# PDM.net
KiCad netlist of a schematic drawn in EAGLE
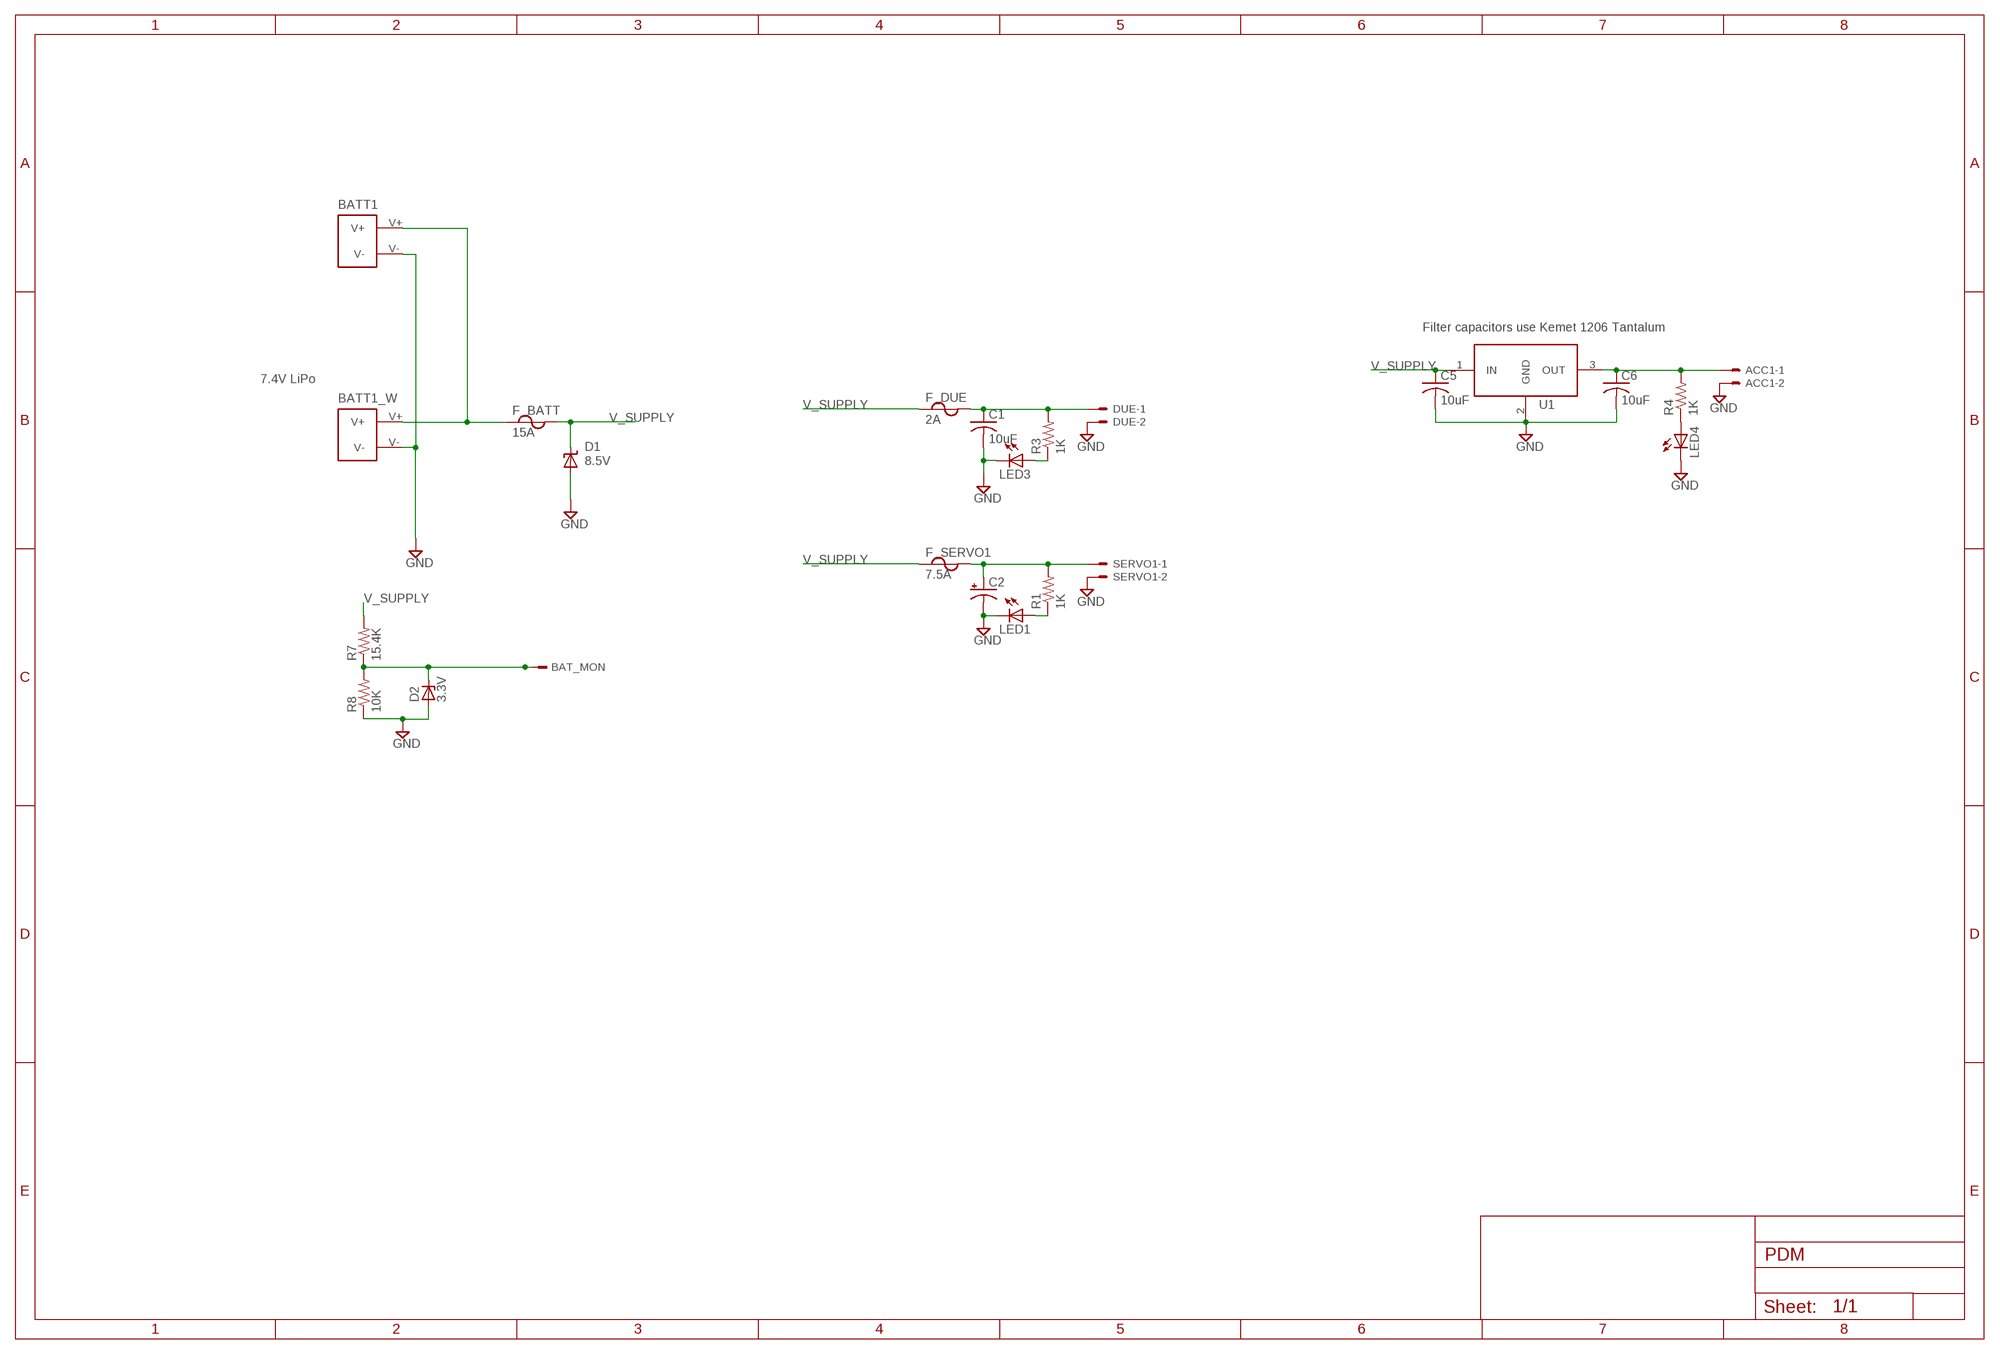
[diagram p0: schematic, sheet 1]

(export (version "E")
  (design (tool "Eeschema 10.0.6"))
  (components
    (comp (ref "ACC1")
      (value "5566-2")
      (footprint "eagle-import:5566-2")
      (libsource (lib "eagle-import") (part "5566-2"))
    )
    (comp (ref "BATT1")
      (value "CON_XT60-PCB_MOUNT")
      (footprint "eagle-import:CON_XT60_PCB_MOUNT")
      (libsource (lib "eagle-import") (part "CON_XT60-PCB_MOUNT"))
    )
    (comp (ref "BATT1_W")
      (value "CON_XT60-PIGTAIL")
      (footprint "eagle-import:CON_XT60_PIGTAIL")
      (libsource (lib "eagle-import") (part "CON_XT60-PIGTAIL"))
    )
    (comp (ref "BAT_MON")
      (value "TSW-101-02-S-S")
      (footprint "eagle-import:TSW-101-02-S-S")
      (libsource (lib "eagle-import") (part "TSW-101-02-S-S"))
    )
    (comp (ref "C1")
      (value "10uF")
      (footprint "eagle-import:C1206K")
      (libsource (lib "eagle-import") (part "C-USC1206K"))
    )
    (comp (ref "C2")
      (value "CPOL-USTT5D11")
      (footprint "eagle-import:TT5D11")
      (libsource (lib "eagle-import") (part "CPOL-USTT5D11"))
    )
    (comp (ref "C5")
      (value "10uF")
      (footprint "eagle-import:C1206K")
      (libsource (lib "eagle-import") (part "C-USC1206K"))
    )
    (comp (ref "C6")
      (value "10uF")
      (footprint "eagle-import:C1206K")
      (libsource (lib "eagle-import") (part "C-USC1206K"))
    )
    (comp (ref "D1")
      (value "8.5V")
      (footprint "eagle-import:SMBJ")
      (libsource (lib "eagle-import") (part "SUPPRESSOR-SMBJ"))
    )
    (comp (ref "D2")
      (value "3.3V")
      (footprint "eagle-import:SMB")
      (libsource (lib "eagle-import") (part "ZENER-DIODESMB"))
    )
    (comp (ref "DUE")
      (value "5566-2")
      (footprint "eagle-import:5566-2")
      (libsource (lib "eagle-import") (part "5566-2"))
    )
    (comp (ref "F_BATT")
      (value "15A")
      (footprint "eagle-import:ATO")
      (libsource (lib "eagle-import") (part "FUSE-ATO"))
    )
    (comp (ref "F_DUE")
      (value "2A")
      (footprint "eagle-import:ATO")
      (libsource (lib "eagle-import") (part "FUSE-ATO"))
    )
    (comp (ref "F_SERVO1")
      (value "7.5A")
      (footprint "eagle-import:ATO")
      (libsource (lib "eagle-import") (part "FUSE-ATO"))
    )
    (comp (ref "LED1")
      (value "LEDSML1206")
      (footprint "eagle-import:SML1206")
      (libsource (lib "eagle-import") (part "LEDSML1206"))
    )
    (comp (ref "LED3")
      (value "LEDSML1206")
      (footprint "eagle-import:SML1206")
      (libsource (lib "eagle-import") (part "LEDSML1206"))
    )
    (comp (ref "LED4")
      (value "LEDSML1206")
      (footprint "eagle-import:SML1206")
      (libsource (lib "eagle-import") (part "LEDSML1206"))
    )
    (comp (ref "R1")
      (value "1K")
      (footprint "eagle-import:R1206")
      (libsource (lib "eagle-import") (part "R-US_R1206"))
    )
    (comp (ref "R3")
      (value "1K")
      (footprint "eagle-import:R1206")
      (libsource (lib "eagle-import") (part "R-US_R1206"))
    )
    (comp (ref "R4")
      (value "1K")
      (footprint "eagle-import:R1206")
      (libsource (lib "eagle-import") (part "R-US_R1206"))
    )
    (comp (ref "R7")
      (value "15.4K")
      (footprint "eagle-import:R1206")
      (libsource (lib "eagle-import") (part "R-US_R1206"))
    )
    (comp (ref "R8")
      (value "10K")
      (footprint "eagle-import:R1206")
      (libsource (lib "eagle-import") (part "R-US_R1206"))
    )
    (comp (ref "SERVO1")
      (value "5566-2")
      (footprint "eagle-import:5566-2")
      (libsource (lib "eagle-import") (part "5566-2"))
    )
    (comp (ref "U1")
      (value "MIC29150/29300/29500VERTICAL")
      (footprint "eagle-import:TO220V")
      (libsource (lib "eagle-import") (part "MIC29150/29300/29500VERTICAL"))
    )
  )
  (nets
    (net (code "1") (name "/V_SUPPLY") (class "Default")
      (node (ref "C5") (pin "1") (pinfunction "1_1") (pintype "passive"))
      (node (ref "D1") (pin "C") (pinfunction "C_C") (pintype "passive"))
      (node (ref "F_BATT") (pin "B1") (pinfunction "2_B1") (pintype "passive"))
      (node (ref "F_BATT") (pin "B2") (pinfunction "2_B2") (pintype "passive"))
      (node (ref "F_BATT") (pin "B3") (pinfunction "2_B3") (pintype "passive"))
      (node (ref "F_BATT") (pin "B4") (pinfunction "2_B4") (pintype "passive"))
      (node (ref "F_DUE") (pin "A1") (pinfunction "1_A1") (pintype "passive"))
      (node (ref "F_DUE") (pin "A2") (pinfunction "1_A2") (pintype "passive"))
      (node (ref "F_DUE") (pin "A3") (pinfunction "1_A3") (pintype "passive"))
      (node (ref "F_DUE") (pin "A4") (pinfunction "1_A4") (pintype "passive"))
      (node (ref "F_SERVO1") (pin "A1") (pinfunction "1_A1") (pintype "passive"))
      (node (ref "F_SERVO1") (pin "A2") (pinfunction "1_A2") (pintype "passive"))
      (node (ref "F_SERVO1") (pin "A3") (pinfunction "1_A3") (pintype "passive"))
      (node (ref "F_SERVO1") (pin "A4") (pinfunction "1_A4") (pintype "passive"))
      (node (ref "R7") (pin "2") (pinfunction "2_2") (pintype "passive"))
      (node (ref "U1") (pin "1") (pinfunction "IN_1") (pintype "bidirectional"))
    )
    (net (code "2") (name "GND") (class "Default")
      (node (ref "ACC1") (pin "2") (pinfunction "S_2") (pintype "passive"))
      (node (ref "BATT1") (pin "V-") (pinfunction "V-_V-") (pintype "bidirectional"))
      (node (ref "BATT1_W") (pin "V-") (pinfunction "V-_V-") (pintype "bidirectional"))
      (node (ref "C1") (pin "2") (pinfunction "2_2") (pintype "passive"))
      (node (ref "C2") (pin "-") (pinfunction "-_-") (pintype "passive"))
      (node (ref "C5") (pin "2") (pinfunction "2_2") (pintype "passive"))
      (node (ref "C6") (pin "2") (pinfunction "2_2") (pintype "passive"))
      (node (ref "D1") (pin "A") (pinfunction "A_A") (pintype "passive"))
      (node (ref "D2") (pin "A") (pinfunction "A_A") (pintype "passive"))
      (node (ref "DUE") (pin "2") (pinfunction "S_2") (pintype "passive"))
      (node (ref "LED1") (pin "C") (pinfunction "C_C") (pintype "passive"))
      (node (ref "LED3") (pin "C") (pinfunction "C_C") (pintype "passive"))
      (node (ref "LED4") (pin "C") (pinfunction "C_C") (pintype "passive"))
      (node (ref "R8") (pin "1") (pinfunction "1_1") (pintype "passive"))
      (node (ref "SERVO1") (pin "2") (pinfunction "S_2") (pintype "passive"))
      (node (ref "U1") (pin "2") (pinfunction "GND_2") (pintype "bidirectional"))
    )
    (net (code "3") (name "Net-(ACC1A-S)") (class "Default")
      (node (ref "ACC1") (pin "1") (pinfunction "S_1") (pintype "passive"))
      (node (ref "C6") (pin "1") (pinfunction "1_1") (pintype "passive"))
      (node (ref "R4") (pin "2") (pinfunction "2_2") (pintype "passive"))
      (node (ref "U1") (pin "3") (pinfunction "OUT_3") (pintype "bidirectional"))
    )
    (net (code "4") (name "Net-(BATT1-PadV+)") (class "Default")
      (node (ref "BATT1") (pin "V+") (pinfunction "V+_V+") (pintype "bidirectional"))
      (node (ref "BATT1_W") (pin "V+") (pinfunction "V+_V+") (pintype "bidirectional"))
      (node (ref "F_BATT") (pin "A1") (pinfunction "1_A1") (pintype "passive"))
      (node (ref "F_BATT") (pin "A2") (pinfunction "1_A2") (pintype "passive"))
      (node (ref "F_BATT") (pin "A3") (pinfunction "1_A3") (pintype "passive"))
      (node (ref "F_BATT") (pin "A4") (pinfunction "1_A4") (pintype "passive"))
    )
    (net (code "5") (name "Net-(BAT_MON-Pad1)") (class "Default")
      (node (ref "BAT_MON") (pin "1") (pinfunction "1_1") (pintype "passive"))
      (node (ref "D2") (pin "C") (pinfunction "C_C") (pintype "passive"))
      (node (ref "R7") (pin "1") (pinfunction "1_1") (pintype "passive"))
      (node (ref "R8") (pin "2") (pinfunction "2_2") (pintype "passive"))
    )
    (net (code "6") (name "Net-(DUEA-S)") (class "Default")
      (node (ref "C1") (pin "1") (pinfunction "1_1") (pintype "passive"))
      (node (ref "DUE") (pin "1") (pinfunction "S_1") (pintype "passive"))
      (node (ref "F_DUE") (pin "B1") (pinfunction "2_B1") (pintype "passive"))
      (node (ref "F_DUE") (pin "B2") (pinfunction "2_B2") (pintype "passive"))
      (node (ref "F_DUE") (pin "B3") (pinfunction "2_B3") (pintype "passive"))
      (node (ref "F_DUE") (pin "B4") (pinfunction "2_B4") (pintype "passive"))
      (node (ref "R3") (pin "2") (pinfunction "2_2") (pintype "passive"))
    )
    (net (code "7") (name "Net-(LED1-PadA)") (class "Default")
      (node (ref "LED1") (pin "A") (pinfunction "A_A") (pintype "passive"))
      (node (ref "R1") (pin "1") (pinfunction "1_1") (pintype "passive"))
    )
    (net (code "8") (name "Net-(LED3-PadA)") (class "Default")
      (node (ref "LED3") (pin "A") (pinfunction "A_A") (pintype "passive"))
      (node (ref "R3") (pin "1") (pinfunction "1_1") (pintype "passive"))
    )
    (net (code "9") (name "Net-(LED4-PadA)") (class "Default")
      (node (ref "LED4") (pin "A") (pinfunction "A_A") (pintype "passive"))
      (node (ref "R4") (pin "1") (pinfunction "1_1") (pintype "passive"))
    )
    (net (code "10") (name "Net-(SERVO1A-S)") (class "Default")
      (node (ref "C2") (pin "+") (pinfunction "+_+") (pintype "passive"))
      (node (ref "F_SERVO1") (pin "B1") (pinfunction "2_B1") (pintype "passive"))
      (node (ref "F_SERVO1") (pin "B2") (pinfunction "2_B2") (pintype "passive"))
      (node (ref "F_SERVO1") (pin "B3") (pinfunction "2_B3") (pintype "passive"))
      (node (ref "F_SERVO1") (pin "B4") (pinfunction "2_B4") (pintype "passive"))
      (node (ref "R1") (pin "2") (pinfunction "2_2") (pintype "passive"))
      (node (ref "SERVO1") (pin "1") (pinfunction "S_1") (pintype "passive"))
    )
  )
)
